# v0-cellphone.net
KiCad netlist of a schematic drawn in EAGLE
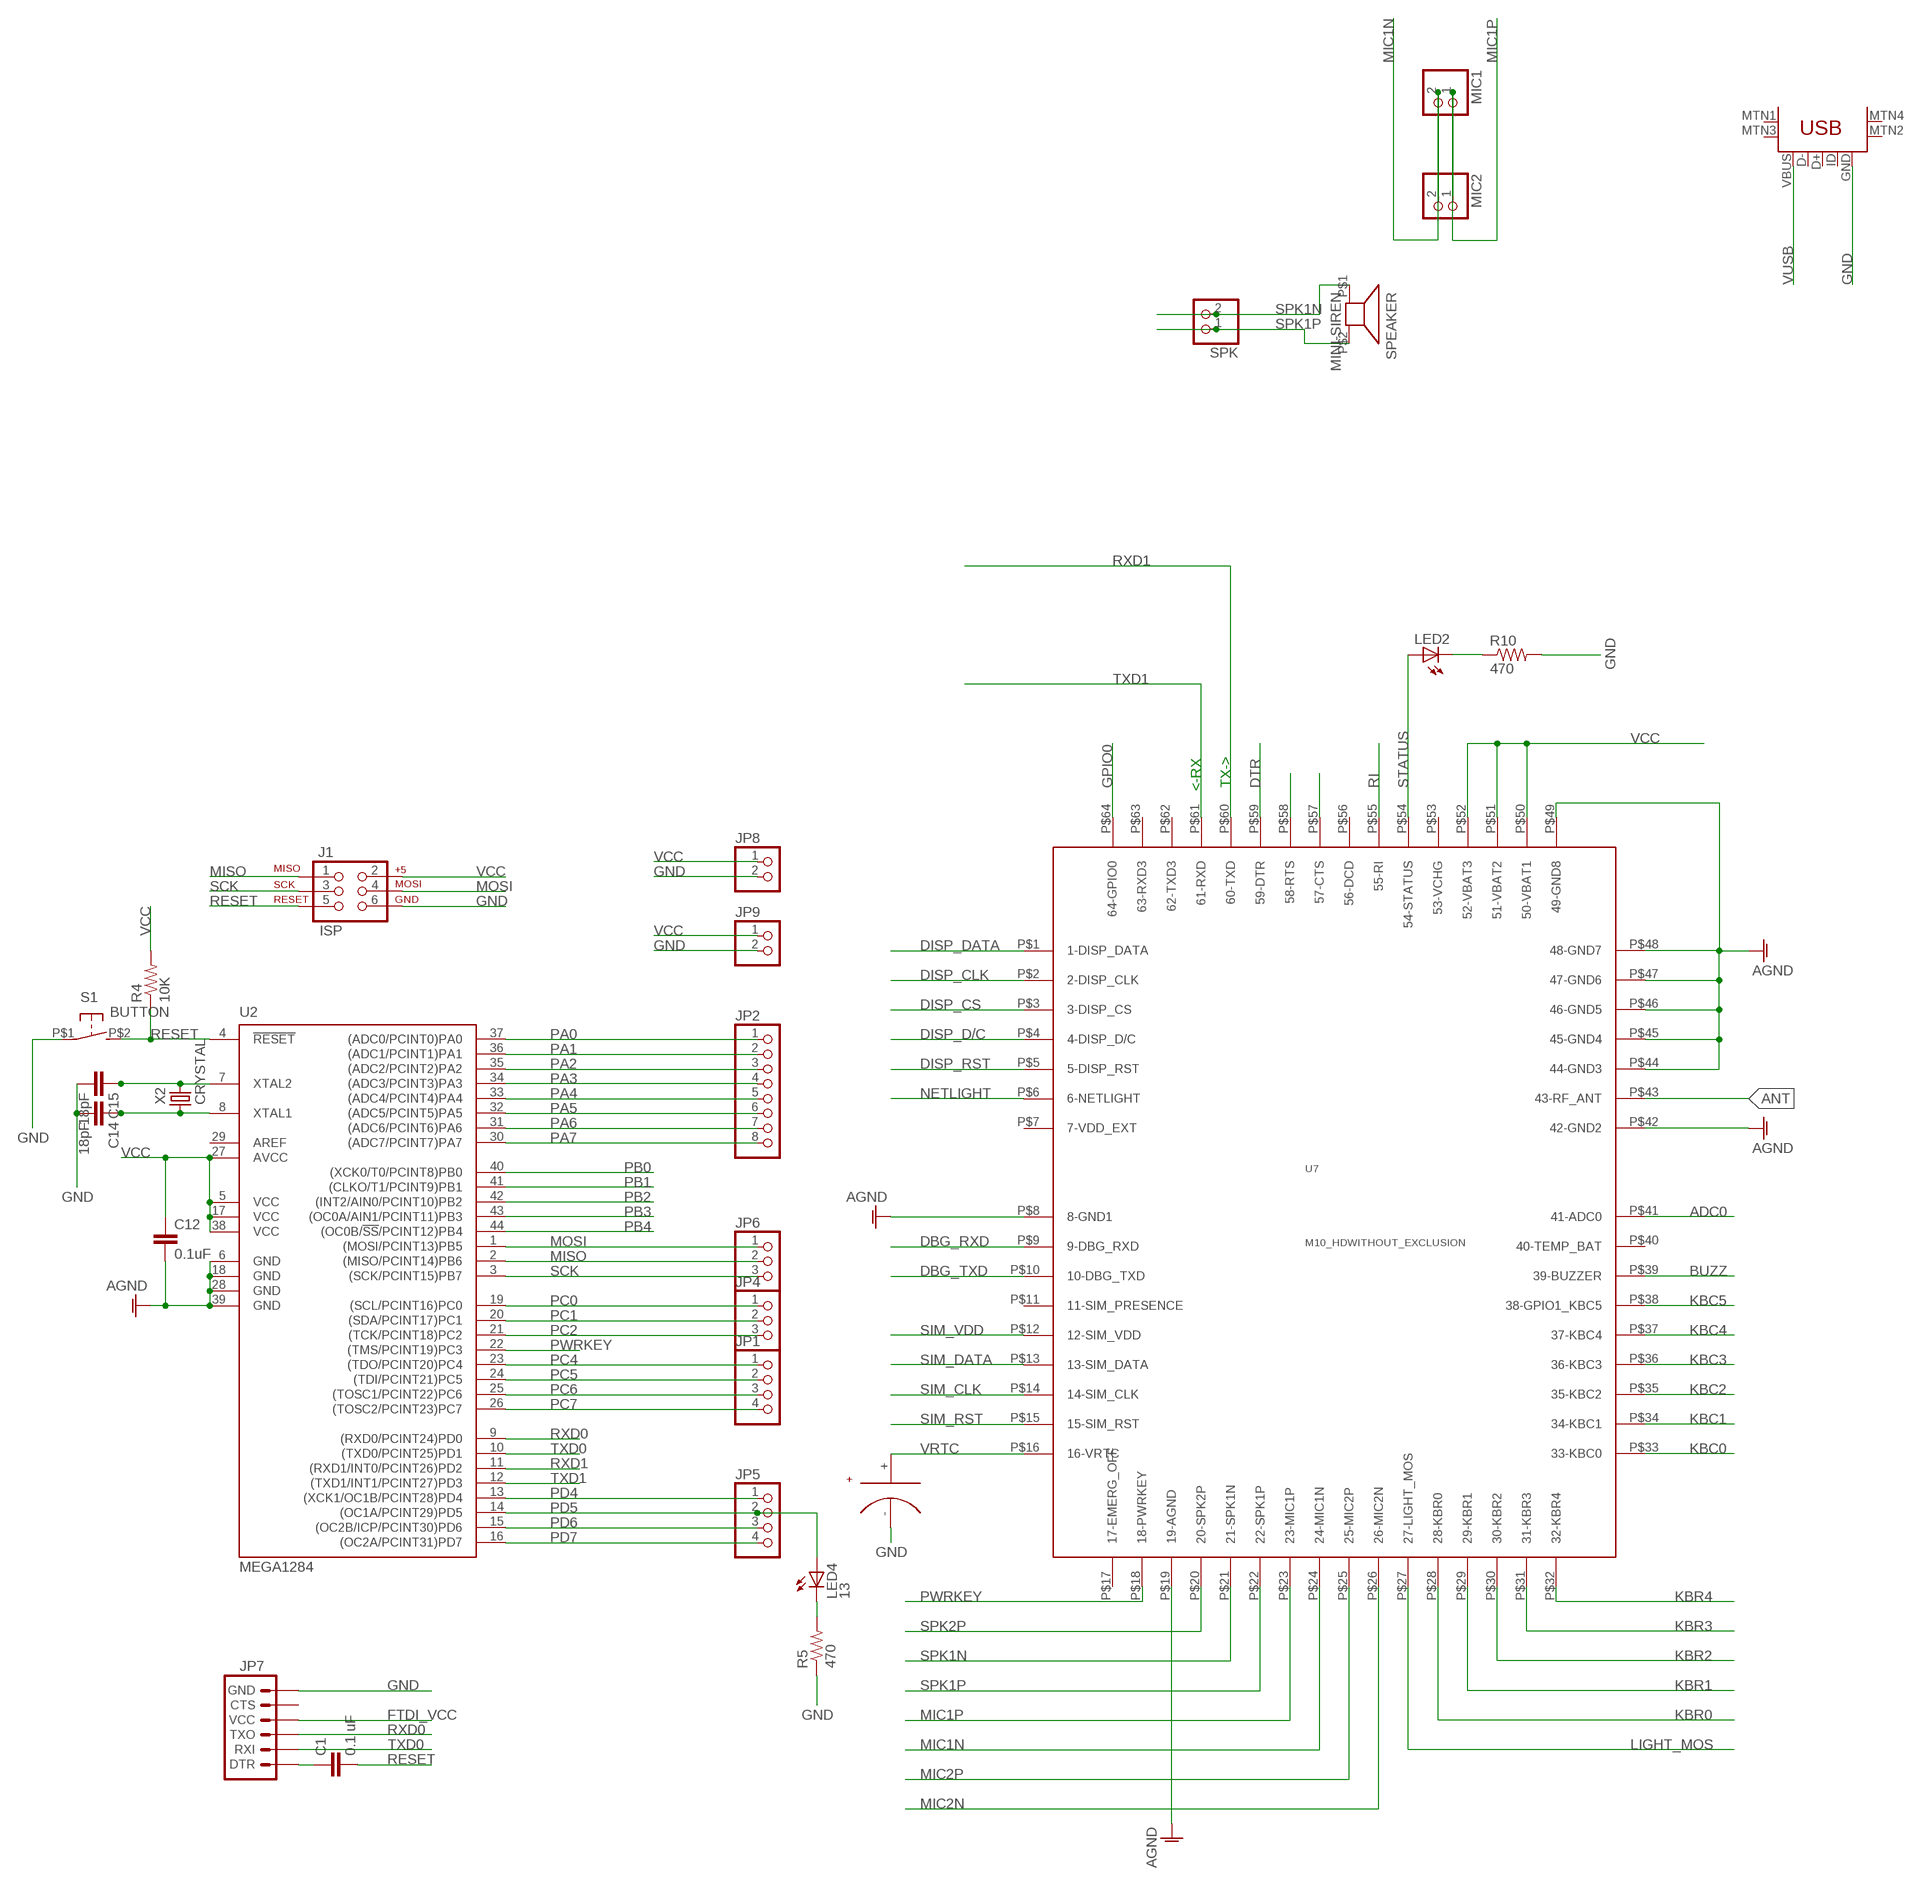
[diagram p0: schematic, sheet 1, part 1 of 2]
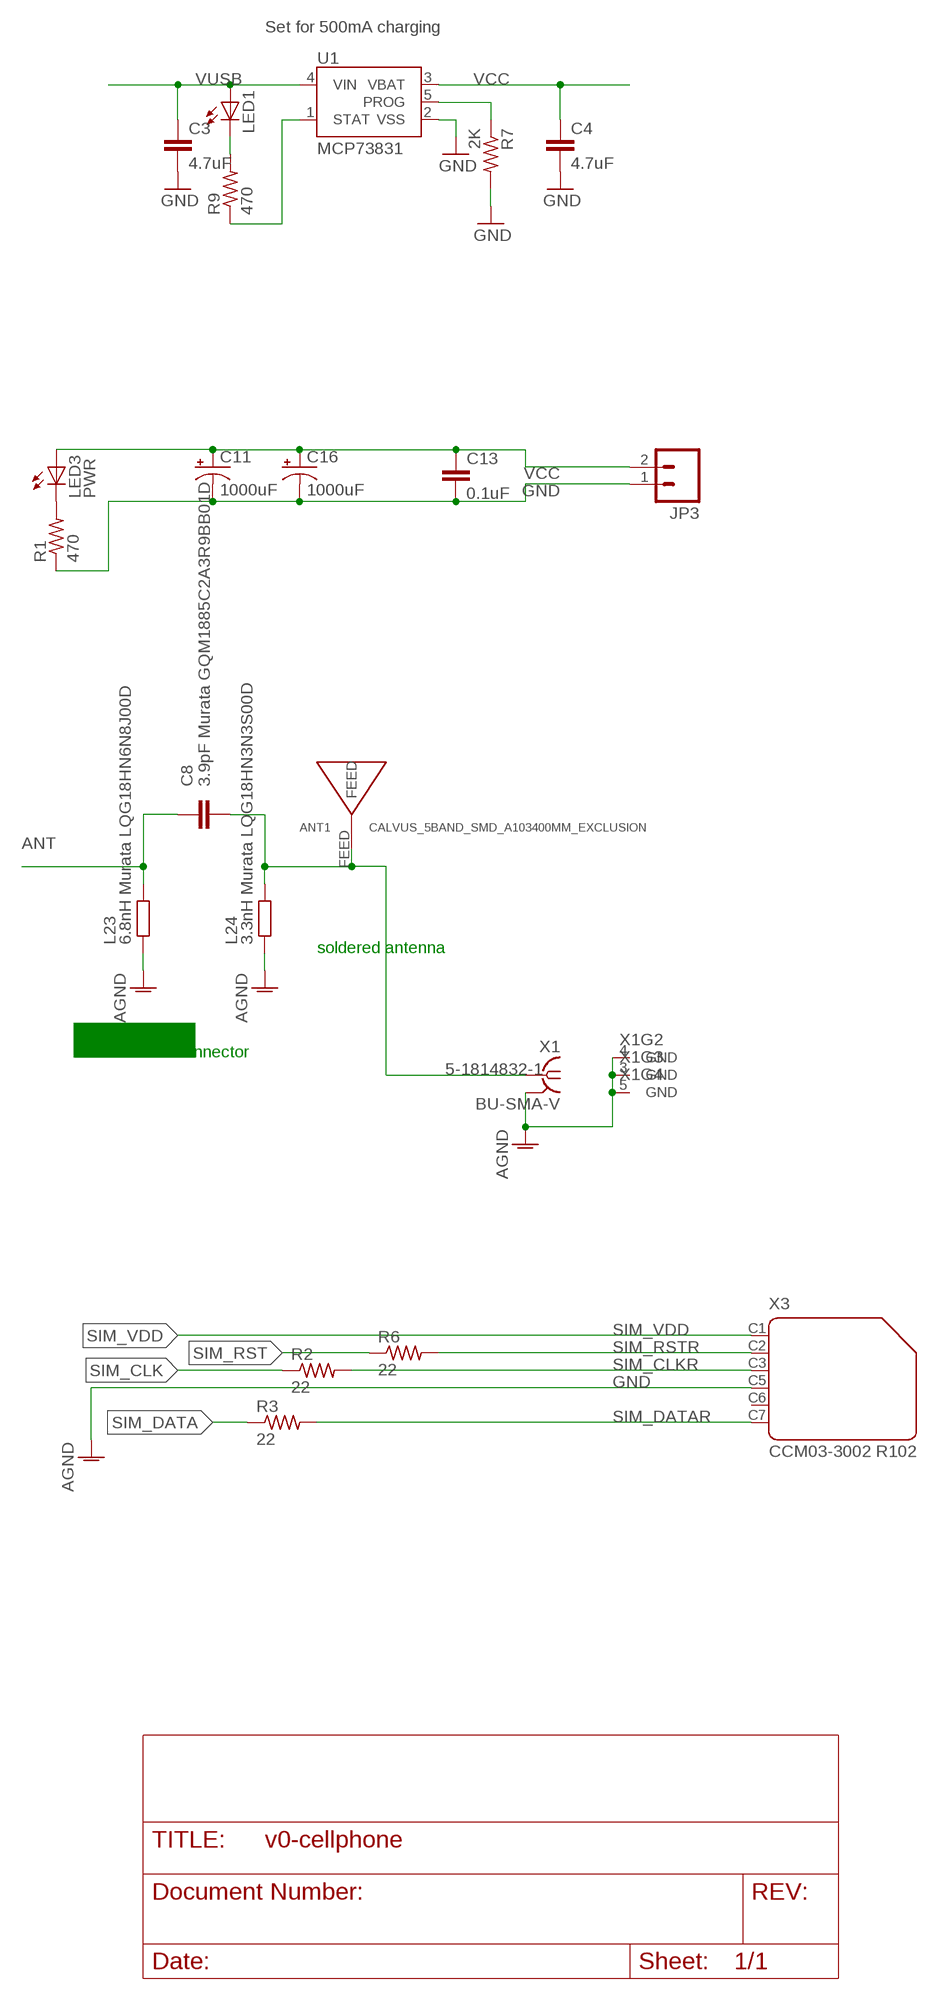
[diagram p1: schematic, sheet 1, part 2 of 2]

(export (version "E")
  (design (tool "Eeschema 10.0.6"))
  (components
    (comp (ref "ANT1")
      (value "CALVUS_5BAND_SMD_A103400MM_EXCLUSION")
      (footprint "eagle-import:CALVUS_5BAND_SMD_A10340_0MM_EXCLUSION")
      (libsource (lib "eagle-import") (part "CALVUS_5BAND_SMD_A103400MM_EXCLUSION"))
    )
    (comp (ref "C1")
      (value "0.1 uF")
      (footprint "eagle-import:C1206")
      (libsource (lib "eagle-import") (part "cellphone-rcl_C-EUC1206"))
    )
    (comp (ref "C2")
      (value "SUPERCAPPAS")
      (footprint "eagle-import:414-VA5R")
      (libsource (lib "eagle-import") (part "SUPERCAPPAS"))
    )
    (comp (ref "C3")
      (value "4.7uF")
      (footprint "eagle-import:C1206")
      (libsource (lib "eagle-import") (part "cellphone-rcl_C-EUC1206"))
    )
    (comp (ref "C4")
      (value "4.7uF")
      (footprint "eagle-import:C1206")
      (libsource (lib "eagle-import") (part "cellphone-rcl_C-EUC1206"))
    )
    (comp (ref "C8")
      (value "3.9pF Murata GQM1885C2A3R9BB01D")
      (footprint "eagle-import:C0603-ROUND")
      (libsource (lib "eagle-import") (part "C-EU0603-RND"))
    )
    (comp (ref "C11")
      (value "1000uF")
      (footprint "eagle-import:D_7343-31R")
      (libsource (lib "eagle-import") (part "CPOL-USD/7343-31R"))
    )
    (comp (ref "C12")
      (value "0.1uF")
      (footprint "eagle-import:C1206")
      (libsource (lib "eagle-import") (part "cellphone-rcl_C-EUC1206"))
    )
    (comp (ref "C13")
      (value "0.1uF")
      (footprint "eagle-import:C1206")
      (libsource (lib "eagle-import") (part "cellphone-rcl_C-EUC1206"))
    )
    (comp (ref "C14")
      (value "18pF")
      (footprint "eagle-import:C1206")
      (libsource (lib "eagle-import") (part "cellphone-rcl_C-EUC1206"))
    )
    (comp (ref "C15")
      (value "18pF")
      (footprint "eagle-import:C1206")
      (libsource (lib "eagle-import") (part "cellphone-rcl_C-EUC1206"))
    )
    (comp (ref "C16")
      (value "1000uF")
      (footprint "eagle-import:D_7343-31R")
      (libsource (lib "eagle-import") (part "CPOL-USD/7343-31R"))
    )
    (comp (ref "J1")
      (value "ISP")
      (footprint "eagle-import:2X3-NS")
      (libsource (lib "eagle-import") (part "AVR_SPI_PRG_6NS"))
    )
    (comp (ref "J2")
      (value "USB-MINIB-5PIN")
      (footprint "eagle-import:USB-MINIB")
      (libsource (lib "eagle-import") (part "USB-MINIB-5PIN"))
    )
    (comp (ref "JP1")
      (value "PINHD-1X4")
      (footprint "eagle-import:1X04")
      (libsource (lib "eagle-import") (part "PINHD-1X4"))
    )
    (comp (ref "JP2")
      (value "PINHD-1X8")
      (footprint "eagle-import:1X08")
      (libsource (lib "eagle-import") (part "PINHD-1X8"))
    )
    (comp (ref "JP3")
      (value "M02-JST-2MM-SMT")
      (footprint "eagle-import:JST-2-SMD")
      (libsource (lib "eagle-import") (part "M02-JST-2MM-SMT"))
    )
    (comp (ref "JP4")
      (value "PINHD-1X3")
      (footprint "eagle-import:1X03")
      (libsource (lib "eagle-import") (part "PINHD-1X3"))
    )
    (comp (ref "JP5")
      (value "PINHD-1X4")
      (footprint "eagle-import:1X04")
      (libsource (lib "eagle-import") (part "PINHD-1X4"))
    )
    (comp (ref "JP6")
      (value "PINHD-1X3")
      (footprint "eagle-import:1X03")
      (libsource (lib "eagle-import") (part "PINHD-1X3"))
    )
    (comp (ref "JP7")
      (value "ARDUINO_SERIAL_PROGRAMSMD-NOHOLES")
      (footprint "eagle-import:1X06-SMD-NOHOLES")
      (libsource (lib "eagle-import") (part "ARDUINO_SERIAL_PROGRAMSMD-NOHOLES"))
    )
    (comp (ref "JP8")
      (value "PINHD-1X2")
      (footprint "eagle-import:1X02")
      (libsource (lib "eagle-import") (part "PINHD-1X2"))
    )
    (comp (ref "JP9")
      (value "PINHD-1X2")
      (footprint "eagle-import:1X02")
      (libsource (lib "eagle-import") (part "PINHD-1X2"))
    )
    (comp (ref "L23")
      (value "6.8nH Murata LQG18HN6N8J00D")
      (footprint "eagle-import:R0603-ROUND")
      (libsource (lib "eagle-import") (part "R-EU_0603-RND"))
    )
    (comp (ref "L24")
      (value "3.3nH Murata LQG18HN3N3S00D")
      (footprint "eagle-import:R0603-ROUND")
      (libsource (lib "eagle-import") (part "R-EU_0603-RND"))
    )
    (comp (ref "LED1")
      (value "LEDSMT1206")
      (footprint "eagle-import:1206")
      (libsource (lib "eagle-import") (part "LEDSMT1206"))
    )
    (comp (ref "LED2")
      (value "LEDSMT1206")
      (footprint "eagle-import:1206")
      (libsource (lib "eagle-import") (part "LEDSMT1206"))
    )
    (comp (ref "LED3")
      (value "PWR")
      (footprint "eagle-import:1206")
      (libsource (lib "eagle-import") (part "LEDSMT1206"))
    )
    (comp (ref "LED4")
      (value "13")
      (footprint "eagle-import:1206")
      (libsource (lib "eagle-import") (part "LEDSMT1206"))
    )
    (comp (ref "MIC1")
      (value "PINHD-1X2")
      (footprint "eagle-import:1X02")
      (libsource (lib "eagle-import") (part "PINHD-1X2"))
    )
    (comp (ref "MIC2")
      (value "PINHD-1X2")
      (footprint "eagle-import:1X02")
      (libsource (lib "eagle-import") (part "PINHD-1X2"))
    )
    (comp (ref "R1")
      (value "470")
      (footprint "eagle-import:R1206")
      (libsource (lib "eagle-import") (part "R-US_R1206"))
    )
    (comp (ref "R2")
      (value "22")
      (footprint "eagle-import:R1206")
      (libsource (lib "eagle-import") (part "R-US_R1206"))
    )
    (comp (ref "R3")
      (value "22")
      (footprint "eagle-import:R1206")
      (libsource (lib "eagle-import") (part "R-US_R1206"))
    )
    (comp (ref "R4")
      (value "10K")
      (footprint "eagle-import:R1206")
      (libsource (lib "eagle-import") (part "R-US_R1206"))
    )
    (comp (ref "R5")
      (value "470")
      (footprint "eagle-import:R1206")
      (libsource (lib "eagle-import") (part "R-US_R1206"))
    )
    (comp (ref "R6")
      (value "22")
      (footprint "eagle-import:R1206")
      (libsource (lib "eagle-import") (part "R-US_R1206"))
    )
    (comp (ref "R7")
      (value "2K")
      (footprint "eagle-import:R1206")
      (libsource (lib "eagle-import") (part "R-US_R1206"))
    )
    (comp (ref "R9")
      (value "470")
      (footprint "eagle-import:R1206")
      (libsource (lib "eagle-import") (part "R-US_R1206"))
    )
    (comp (ref "R10")
      (value "470")
      (footprint "eagle-import:R1206")
      (libsource (lib "eagle-import") (part "R-US_R1206"))
    )
    (comp (ref "S1")
      (value "BUTTON")
      (footprint "eagle-import:B3U-1000P")
      (libsource (lib "eagle-import") (part "BUTTON-2"))
    )
    (comp (ref "SPEAKER")
      (value "MINI-SIREN")
      (footprint "eagle-import:SPEAKER-6.4MM")
      (libsource (lib "eagle-import") (part "MINI-SIREN"))
    )
    (comp (ref "SPK")
      (value "PINHD-1X2")
      (footprint "eagle-import:1X02")
      (libsource (lib "eagle-import") (part "PINHD-1X2"))
    )
    (comp (ref "U1")
      (value "MCP73831")
      (footprint "eagle-import:SOT23-5")
      (libsource (lib "eagle-import") (part "MCP73831"))
    )
    (comp (ref "U2")
      (value "MEGA1284")
      (footprint "eagle-import:TQFP44")
      (libsource (lib "eagle-import") (part "MEGA164P/324P/644P-AU"))
    )
    (comp (ref "U7")
      (value "M10_HDWITHOUT_EXCLUSION")
      (footprint "eagle-import:M10_HD_WITHOUT_EXCLUSION")
      (libsource (lib "eagle-import") (part "M10_HDWITHOUT_EXCLUSION"))
    )
    (comp (ref "X1")
      (value "BU-SMA-V")
      (footprint "eagle-import:BU-SMA-V")
      (fields (field (name "PN") "5-1814832-1"))
      (libsource (lib "eagle-import") (part "BU-SMA-V"))
    )
    (comp (ref "X2")
      (value "CRYSTAL")
      (footprint "eagle-import:2-SMD-5X3MM")
      (libsource (lib "eagle-import") (part "CRYSTAL"))
    )
    (comp (ref "X3")
      (value "CCM03-3002 R102")
      (footprint "eagle-import:CON-AMPHENOL_C707_10M006_512_2")
      (fields (field (name "OC_FARNELL") "1463072 "))
      (libsource (lib "eagle-import") (part "CON-AMPHENOL_SIMLOCK-C707_10M006_512_2"))
    )
  )
  (nets
    (net (code "1") (name "/ADC0") (class "Default")
      (node (ref "U7") (pin "P$41") (pinfunction "41-ADC0_P$41") (pintype "bidirectional"))
    )
    (net (code "2") (name "/AREF") (class "Default")
      (node (ref "U2") (pin "29") (pinfunction "AREF_29") (pintype "power_in"))
    )
    (net (code "3") (name "/BUZZ") (class "Default")
      (node (ref "U7") (pin "P$39") (pinfunction "39-BUZZER_P$39") (pintype "bidirectional"))
    )
    (net (code "4") (name "/DBG_RXD") (class "Default")
      (node (ref "U7") (pin "P$9") (pinfunction "9-DBG_RXD_P$9") (pintype "bidirectional"))
    )
    (net (code "5") (name "/DBG_TXD") (class "Default")
      (node (ref "U7") (pin "P$10") (pinfunction "10-DBG_TXD_P$10") (pintype "bidirectional"))
    )
    (net (code "6") (name "/DISP_CLK") (class "Default")
      (node (ref "U7") (pin "P$2") (pinfunction "2-DISP_CLK_P$2") (pintype "bidirectional"))
    )
    (net (code "7") (name "/DISP_CS") (class "Default")
      (node (ref "U7") (pin "P$3") (pinfunction "3-DISP_CS_P$3") (pintype "bidirectional"))
    )
    (net (code "8") (name "/DISP_DATA") (class "Default")
      (node (ref "U7") (pin "P$1") (pinfunction "1-DISP_DATA_P$1") (pintype "bidirectional"))
    )
    (net (code "9") (name "/DISP_D{slash}C") (class "Default")
      (node (ref "U7") (pin "P$4") (pinfunction "4-DISP_D/C_P$4") (pintype "bidirectional"))
    )
    (net (code "10") (name "/DISP_RST") (class "Default")
      (node (ref "U7") (pin "P$5") (pinfunction "5-DISP_RST_P$5") (pintype "bidirectional"))
    )
    (net (code "11") (name "/DTR") (class "Default")
      (node (ref "U7") (pin "P$59") (pinfunction "59-DTR_P$59") (pintype "bidirectional"))
    )
    (net (code "12") (name "/FTDI_VCC") (class "Default")
      (node (ref "JP7") (pin "4") (pinfunction "VCC_4") (pintype "passive"))
    )
    (net (code "13") (name "/GPIO0") (class "Default")
      (node (ref "U7") (pin "P$64") (pinfunction "64-GPIO0_P$64") (pintype "bidirectional"))
    )
    (net (code "14") (name "/KBC0") (class "Default")
      (node (ref "U7") (pin "P$33") (pinfunction "33-KBC0_P$33") (pintype "bidirectional"))
    )
    (net (code "15") (name "/KBC1") (class "Default")
      (node (ref "U7") (pin "P$34") (pinfunction "34-KBC1_P$34") (pintype "bidirectional"))
    )
    (net (code "16") (name "/KBC2") (class "Default")
      (node (ref "U7") (pin "P$35") (pinfunction "35-KBC2_P$35") (pintype "bidirectional"))
    )
    (net (code "17") (name "/KBC3") (class "Default")
      (node (ref "U7") (pin "P$36") (pinfunction "36-KBC3_P$36") (pintype "bidirectional"))
    )
    (net (code "18") (name "/KBC4") (class "Default")
      (node (ref "U7") (pin "P$37") (pinfunction "37-KBC4_P$37") (pintype "bidirectional"))
    )
    (net (code "19") (name "/KBC5") (class "Default")
      (node (ref "U7") (pin "P$38") (pinfunction "38-GPIO1_KBC5_P$38") (pintype "bidirectional"))
    )
    (net (code "20") (name "/KBR0") (class "Default")
      (node (ref "U7") (pin "P$28") (pinfunction "28-KBR0_P$28") (pintype "bidirectional"))
    )
    (net (code "21") (name "/KBR1") (class "Default")
      (node (ref "U7") (pin "P$29") (pinfunction "29-KBR1_P$29") (pintype "bidirectional"))
    )
    (net (code "22") (name "/KBR2") (class "Default")
      (node (ref "U7") (pin "P$30") (pinfunction "30-KBR2_P$30") (pintype "bidirectional"))
    )
    (net (code "23") (name "/KBR3") (class "Default")
      (node (ref "U7") (pin "P$31") (pinfunction "31-KBR3_P$31") (pintype "bidirectional"))
    )
    (net (code "24") (name "/KBR4") (class "Default")
      (node (ref "U7") (pin "P$32") (pinfunction "32-KBR4_P$32") (pintype "bidirectional"))
    )
    (net (code "25") (name "/LIGHT_MOS") (class "Default")
      (node (ref "U7") (pin "P$27") (pinfunction "27-LIGHT_MOS_P$27") (pintype "bidirectional"))
    )
    (net (code "26") (name "/MIC1N") (class "Default")
      (node (ref "MIC1") (pin "2") (pinfunction "2_2") (pintype "passive"))
      (node (ref "MIC2") (pin "2") (pinfunction "2_2") (pintype "passive"))
      (node (ref "U7") (pin "P$24") (pinfunction "24-MIC1N_P$24") (pintype "bidirectional"))
    )
    (net (code "27") (name "/MIC1P") (class "Default")
      (node (ref "MIC1") (pin "1") (pinfunction "1_1") (pintype "passive"))
      (node (ref "MIC2") (pin "1") (pinfunction "1_1") (pintype "passive"))
      (node (ref "U7") (pin "P$23") (pinfunction "23-MIC1P_P$23") (pintype "bidirectional"))
    )
    (net (code "28") (name "/MIC2N") (class "Default")
      (node (ref "U7") (pin "P$26") (pinfunction "26-MIC2N_P$26") (pintype "bidirectional"))
    )
    (net (code "29") (name "/MIC2P") (class "Default")
      (node (ref "U7") (pin "P$25") (pinfunction "25-MIC2P_P$25") (pintype "bidirectional"))
    )
    (net (code "30") (name "/MISO") (class "Default")
      (node (ref "J1") (pin "1") (pinfunction "1_1") (pintype "passive"))
      (node (ref "JP6") (pin "2") (pinfunction "2_2") (pintype "passive"))
      (node (ref "U2") (pin "2") (pinfunction "(MISO/PCINT14)PB6_2") (pintype "bidirectional"))
    )
    (net (code "31") (name "/MOSI") (class "Default")
      (node (ref "J1") (pin "4") (pinfunction "4_4") (pintype "passive"))
      (node (ref "JP6") (pin "1") (pinfunction "1_1") (pintype "passive"))
      (node (ref "U2") (pin "1") (pinfunction "(MOSI/PCINT13)PB5_1") (pintype "bidirectional"))
    )
    (net (code "32") (name "/NETLIGHT") (class "Default")
      (node (ref "U7") (pin "P$6") (pinfunction "6-NETLIGHT_P$6") (pintype "bidirectional"))
    )
    (net (code "33") (name "/PA0") (class "Default")
      (node (ref "JP2") (pin "1") (pinfunction "1_1") (pintype "passive"))
      (node (ref "U2") (pin "37") (pinfunction "(ADC0/PCINT0)PA0_37") (pintype "bidirectional"))
    )
    (net (code "34") (name "/PA1") (class "Default")
      (node (ref "JP2") (pin "2") (pinfunction "2_2") (pintype "passive"))
      (node (ref "U2") (pin "36") (pinfunction "(ADC1/PCINT1)PA1_36") (pintype "bidirectional"))
    )
    (net (code "35") (name "/PA2") (class "Default")
      (node (ref "JP2") (pin "3") (pinfunction "3_3") (pintype "passive"))
      (node (ref "U2") (pin "35") (pinfunction "(ADC2/PCINT2)PA2_35") (pintype "bidirectional"))
    )
    (net (code "36") (name "/PA3") (class "Default")
      (node (ref "JP2") (pin "4") (pinfunction "4_4") (pintype "passive"))
      (node (ref "U2") (pin "34") (pinfunction "(ADC3/PCINT3)PA3_34") (pintype "bidirectional"))
    )
    (net (code "37") (name "/PA4") (class "Default")
      (node (ref "JP2") (pin "5") (pinfunction "5_5") (pintype "passive"))
      (node (ref "U2") (pin "33") (pinfunction "(ADC4/PCINT4)PA4_33") (pintype "bidirectional"))
    )
    (net (code "38") (name "/PA5") (class "Default")
      (node (ref "JP2") (pin "6") (pinfunction "6_6") (pintype "passive"))
      (node (ref "U2") (pin "32") (pinfunction "(ADC5/PCINT5)PA5_32") (pintype "bidirectional"))
    )
    (net (code "39") (name "/PA6") (class "Default")
      (node (ref "JP2") (pin "7") (pinfunction "7_7") (pintype "passive"))
      (node (ref "U2") (pin "31") (pinfunction "(ADC6/PCINT6)PA6_31") (pintype "bidirectional"))
    )
    (net (code "40") (name "/PA7") (class "Default")
      (node (ref "JP2") (pin "8") (pinfunction "8_8") (pintype "passive"))
      (node (ref "U2") (pin "30") (pinfunction "(ADC7/PCINT7)PA7_30") (pintype "bidirectional"))
    )
    (net (code "41") (name "/PB0") (class "Default")
      (node (ref "U2") (pin "40") (pinfunction "(XCK0/T0/PCINT8)PB0_40") (pintype "bidirectional"))
    )
    (net (code "42") (name "/PB1") (class "Default")
      (node (ref "U2") (pin "41") (pinfunction "(CLKO/T1/PCINT9)PB1_41") (pintype "bidirectional"))
    )
    (net (code "43") (name "/PB2") (class "Default")
      (node (ref "U2") (pin "42") (pinfunction "(INT2/AIN0/PCINT10)PB2_42") (pintype "bidirectional"))
    )
    (net (code "44") (name "/PB3") (class "Default")
      (node (ref "U2") (pin "43") (pinfunction "(OC0A/AIN1/PCINT11)PB3_43") (pintype "bidirectional"))
    )
    (net (code "45") (name "/PB4") (class "Default")
      (node (ref "U2") (pin "44") (pinfunction "(OC0B/~{SS}/PCINT12)PB4_44") (pintype "bidirectional"))
    )
    (net (code "46") (name "/PC0") (class "Default")
      (node (ref "JP4") (pin "1") (pinfunction "1_1") (pintype "passive"))
      (node (ref "U2") (pin "19") (pinfunction "(SCL/PCINT16)PC0_19") (pintype "bidirectional"))
    )
    (net (code "47") (name "/PC1") (class "Default")
      (node (ref "JP4") (pin "2") (pinfunction "2_2") (pintype "passive"))
      (node (ref "U2") (pin "20") (pinfunction "(SDA/PCINT17)PC1_20") (pintype "bidirectional"))
    )
    (net (code "48") (name "/PC2") (class "Default")
      (node (ref "JP4") (pin "3") (pinfunction "3_3") (pintype "passive"))
      (node (ref "U2") (pin "21") (pinfunction "(TCK/PCINT18)PC2_21") (pintype "bidirectional"))
    )
    (net (code "49") (name "/PC4") (class "Default")
      (node (ref "JP1") (pin "1") (pinfunction "1_1") (pintype "passive"))
      (node (ref "U2") (pin "23") (pinfunction "(TDO/PCINT20)PC4_23") (pintype "bidirectional"))
    )
    (net (code "50") (name "/PC5") (class "Default")
      (node (ref "JP1") (pin "2") (pinfunction "2_2") (pintype "passive"))
      (node (ref "U2") (pin "24") (pinfunction "(TDI/PCINT21)PC5_24") (pintype "bidirectional"))
    )
    (net (code "51") (name "/PC6") (class "Default")
      (node (ref "JP1") (pin "3") (pinfunction "3_3") (pintype "passive"))
      (node (ref "U2") (pin "25") (pinfunction "(TOSC1/PCINT22)PC6_25") (pintype "bidirectional"))
    )
    (net (code "52") (name "/PC7") (class "Default")
      (node (ref "JP1") (pin "4") (pinfunction "4_4") (pintype "passive"))
      (node (ref "U2") (pin "26") (pinfunction "(TOSC2/PCINT23)PC7_26") (pintype "bidirectional"))
    )
    (net (code "53") (name "/PD4") (class "Default")
      (node (ref "JP5") (pin "1") (pinfunction "1_1") (pintype "passive"))
      (node (ref "U2") (pin "13") (pinfunction "(XCK1/OC1B/PCINT28)PD4_13") (pintype "bidirectional"))
    )
    (net (code "54") (name "/PD5") (class "Default")
      (node (ref "JP5") (pin "2") (pinfunction "2_2") (pintype "passive"))
      (node (ref "LED4") (pin "A") (pinfunction "A_A") (pintype "passive"))
      (node (ref "U2") (pin "14") (pinfunction "(OC1A/PCINT29)PD5_14") (pintype "bidirectional"))
    )
    (net (code "55") (name "/PD6") (class "Default")
      (node (ref "JP5") (pin "3") (pinfunction "3_3") (pintype "passive"))
      (node (ref "U2") (pin "15") (pinfunction "(OC2B/ICP/PCINT30)PD6_15") (pintype "bidirectional"))
    )
    (net (code "56") (name "/PD7") (class "Default")
      (node (ref "JP5") (pin "4") (pinfunction "4_4") (pintype "passive"))
      (node (ref "U2") (pin "16") (pinfunction "(OC2A/PCINT31)PD7_16") (pintype "bidirectional"))
    )
    (net (code "57") (name "/PWRKEY") (class "Default")
      (node (ref "U2") (pin "22") (pinfunction "(TMS/PCINT19)PC3_22") (pintype "bidirectional"))
      (node (ref "U7") (pin "P$18") (pinfunction "18-PWRKEY_P$18") (pintype "bidirectional"))
    )
    (net (code "58") (name "/RESET") (class "Default")
      (node (ref "C1") (pin "2") (pinfunction "2_2") (pintype "passive"))
      (node (ref "J1") (pin "5") (pinfunction "5_5") (pintype "passive"))
      (node (ref "R4") (pin "1") (pinfunction "1_1") (pintype "passive"))
      (node (ref "S1") (pin "P$2") (pinfunction "S_P$2") (pintype "passive"))
      (node (ref "U2") (pin "4") (pinfunction "~{RESET}_4") (pintype "input"))
    )
    (net (code "59") (name "/RI") (class "Default")
      (node (ref "U7") (pin "P$55") (pinfunction "55-RI_P$55") (pintype "bidirectional"))
    )
    (net (code "60") (name "/RXD0") (class "Default")
      (node (ref "JP7") (pin "3") (pinfunction "TXO_3") (pintype "passive"))
      (node (ref "U2") (pin "9") (pinfunction "(RXD0/PCINT24)PD0_9") (pintype "bidirectional"))
    )
    (net (code "61") (name "/RXD1") (class "Default")
      (node (ref "U2") (pin "11") (pinfunction "(RXD1/INT0/PCINT26)PD2_11") (pintype "bidirectional"))
      (node (ref "U7") (pin "P$60") (pinfunction "60-TXD_P$60") (pintype "bidirectional"))
    )
    (net (code "62") (name "/SCK") (class "Default")
      (node (ref "J1") (pin "3") (pinfunction "3_3") (pintype "passive"))
      (node (ref "JP6") (pin "3") (pinfunction "3_3") (pintype "passive"))
      (node (ref "U2") (pin "3") (pinfunction "(SCK/PCINT15)PB7_3") (pintype "bidirectional"))
    )
    (net (code "63") (name "/SIM_CLKR") (class "Default")
      (node (ref "R2") (pin "2") (pinfunction "2_2") (pintype "passive"))
      (node (ref "X3") (pin "C3") (pinfunction "3_C3") (pintype "passive"))
    )
    (net (code "64") (name "/SIM_DATAR") (class "Default")
      (node (ref "R3") (pin "2") (pinfunction "2_2") (pintype "passive"))
      (node (ref "X3") (pin "C7") (pinfunction "6_C7") (pintype "passive"))
    )
    (net (code "65") (name "/SIM_RSTR") (class "Default")
      (node (ref "R6") (pin "2") (pinfunction "2_2") (pintype "passive"))
      (node (ref "X3") (pin "C2") (pinfunction "2_C2") (pintype "passive"))
    )
    (net (code "66") (name "/SPK1N") (class "Default")
      (node (ref "SPEAKER") (pin "P$1") (pinfunction "1_P$1") (pintype "passive"))
      (node (ref "SPK") (pin "2") (pinfunction "2_2") (pintype "passive"))
      (node (ref "U7") (pin "P$21") (pinfunction "21-SPK1N_P$21") (pintype "bidirectional"))
    )
    (net (code "67") (name "/SPK1P") (class "Default")
      (node (ref "SPEAKER") (pin "P$2") (pinfunction "2_P$2") (pintype "passive"))
      (node (ref "SPK") (pin "1") (pinfunction "1_1") (pintype "passive"))
      (node (ref "U7") (pin "P$22") (pinfunction "22-SPK1P_P$22") (pintype "bidirectional"))
    )
    (net (code "68") (name "/SPK2P") (class "Default")
      (node (ref "U7") (pin "P$20") (pinfunction "20-SPK2P_P$20") (pintype "bidirectional"))
    )
    (net (code "69") (name "/STATUS") (class "Default")
      (node (ref "LED2") (pin "A") (pinfunction "A_A") (pintype "passive"))
      (node (ref "U7") (pin "P$54") (pinfunction "54-STATUS_P$54") (pintype "bidirectional"))
    )
    (net (code "70") (name "/TXD0") (class "Default")
      (node (ref "JP7") (pin "2") (pinfunction "RXI_2") (pintype "passive"))
      (node (ref "U2") (pin "10") (pinfunction "(TXD0/PCINT25)PD1_10") (pintype "bidirectional"))
    )
    (net (code "71") (name "/TXD1") (class "Default")
      (node (ref "U2") (pin "12") (pinfunction "(TXD1/INT1/PCINT27)PD3_12") (pintype "bidirectional"))
      (node (ref "U7") (pin "P$61") (pinfunction "61-RXD_P$61") (pintype "bidirectional"))
    )
    (net (code "72") (name "/VCC") (class "Default")
      (node (ref "C11") (pin "+") (pinfunction "+_+") (pintype "passive"))
      (node (ref "C12") (pin "1") (pinfunction "1_1") (pintype "passive"))
      (node (ref "C13") (pin "1") (pinfunction "1_1") (pintype "passive"))
      (node (ref "C16") (pin "+") (pinfunction "+_+") (pintype "passive"))
      (node (ref "C4") (pin "1") (pinfunction "1_1") (pintype "passive"))
      (node (ref "J1") (pin "2") (pinfunction "2_2") (pintype "passive"))
      (node (ref "JP3") (pin "2") (pinfunction "1_2") (pintype "passive"))
      (node (ref "JP8") (pin "1") (pinfunction "1_1") (pintype "passive"))
      (node (ref "JP9") (pin "1") (pinfunction "1_1") (pintype "passive"))
      (node (ref "LED3") (pin "A") (pinfunction "A_A") (pintype "passive"))
      (node (ref "R4") (pin "2") (pinfunction "2_2") (pintype "passive"))
      (node (ref "U1") (pin "3") (pinfunction "VBAT_3") (pintype "power_in"))
      (node (ref "U2") (pin "17") (pinfunction "VCC_17") (pintype "power_in"))
      (node (ref "U2") (pin "27") (pinfunction "AVCC_27") (pintype "power_in"))
      (node (ref "U2") (pin "38") (pinfunction "VCC_38") (pintype "power_in"))
      (node (ref "U2") (pin "5") (pinfunction "VCC_5") (pintype "power_in"))
      (node (ref "U7") (pin "P$50") (pinfunction "50-VBAT1_P$50") (pintype "bidirectional"))
      (node (ref "U7") (pin "P$51") (pinfunction "51-VBAT2_P$51") (pintype "bidirectional"))
      (node (ref "U7") (pin "P$52") (pinfunction "52-VBAT3_P$52") (pintype "bidirectional"))
    )
    (net (code "73") (name "/VRTC") (class "Default")
      (node (ref "C2") (pin "+") (pinfunction "+_+") (pintype "bidirectional"))
      (node (ref "U7") (pin "P$16") (pinfunction "16-VRTC_P$16") (pintype "bidirectional"))
    )
    (net (code "74") (name "/VUSB") (class "Default")
      (node (ref "C3") (pin "1") (pinfunction "1_1") (pintype "passive"))
      (node (ref "J2") (pin "VBUS") (pinfunction "VBUS_VBUS") (pintype "bidirectional"))
      (node (ref "LED1") (pin "A") (pinfunction "A_A") (pintype "passive"))
      (node (ref "U1") (pin "4") (pinfunction "VIN_4") (pintype "power_in"))
    )
    (net (code "75") (name "AGND") (class "Default")
      (node (ref "C11") (pin "-") (pinfunction "-_-") (pintype "passive"))
      (node (ref "C12") (pin "2") (pinfunction "2_2") (pintype "passive"))
      (node (ref "C13") (pin "2") (pinfunction "2_2") (pintype "passive"))
      (node (ref "C14") (pin "2") (pinfunction "2_2") (pintype "passive"))
      (node (ref "C15") (pin "2") (pinfunction "2_2") (pintype "passive"))
      (node (ref "C16") (pin "-") (pinfunction "-_-") (pintype "passive"))
      (node (ref "C2") (pin "-") (pinfunction "-_-") (pintype "bidirectional"))
      (node (ref "C3") (pin "2") (pinfunction "2_2") (pintype "passive"))
      (node (ref "C4") (pin "2") (pinfunction "2_2") (pintype "passive"))
      (node (ref "J1") (pin "6") (pinfunction "6_6") (pintype "passive"))
      (node (ref "J2") (pin "GND") (pinfunction "GND_GND") (pintype "bidirectional"))
      (node (ref "JP3") (pin "1") (pinfunction "2_1") (pintype "passive"))
      (node (ref "JP7") (pin "6") (pinfunction "GND_6") (pintype "passive"))
      (node (ref "JP8") (pin "2") (pinfunction "2_2") (pintype "passive"))
      (node (ref "JP9") (pin "2") (pinfunction "2_2") (pintype "passive"))
      (node (ref "L23") (pin "1") (pinfunction "1_1") (pintype "passive"))
      (node (ref "L24") (pin "1") (pinfunction "1_1") (pintype "passive"))
      (node (ref "R1") (pin "1") (pinfunction "1_1") (pintype "passive"))
      (node (ref "R10") (pin "2") (pinfunction "2_2") (pintype "passive"))
      (node (ref "R5") (pin "1") (pinfunction "1_1") (pintype "passive"))
      (node (ref "R7") (pin "2") (pinfunction "2_2") (pintype "passive"))
      (node (ref "S1") (pin "P$1") (pinfunction "P_P$1") (pintype "passive"))
      (node (ref "U1") (pin "2") (pinfunction "VSS_2") (pintype "power_in"))
      (node (ref "U2") (pin "18") (pinfunction "GND_18") (pintype "power_in"))
      (node (ref "U2") (pin "28") (pinfunction "GND_28") (pintype "power_in"))
      (node (ref "U2") (pin "39") (pinfunction "GND_39") (pintype "power_in"))
      (node (ref "U2") (pin "6") (pinfunction "GND_6") (pintype "power_in"))
      (node (ref "U7") (pin "P$19") (pinfunction "19-AGND_P$19") (pintype "bidirectional"))
      (node (ref "U7") (pin "P$42") (pinfunction "42-GND2_P$42") (pintype "bidirectional"))
      (node (ref "U7") (pin "P$44") (pinfunction "44-GND3_P$44") (pintype "bidirectional"))
      (node (ref "U7") (pin "P$45") (pinfunction "45-GND4_P$45") (pintype "bidirectional"))
      (node (ref "U7") (pin "P$46") (pinfunction "46-GND5_P$46") (pintype "bidirectional"))
      (node (ref "U7") (pin "P$47") (pinfunction "47-GND6_P$47") (pintype "bidirectional"))
      (node (ref "U7") (pin "P$48") (pinfunction "48-GND7_P$48") (pintype "bidirectional"))
      (node (ref "U7") (pin "P$49") (pinfunction "49-GND8_P$49") (pintype "bidirectional"))
      (node (ref "U7") (pin "P$8") (pinfunction "8-GND1_P$8") (pintype "bidirectional"))
      (node (ref "X1") (pin "2") (pinfunction "GND_2") (pintype "power_in"))
      (node (ref "X1") (pin "3") (pinfunction "GND_3") (pintype "power_in"))
      (node (ref "X1") (pin "4") (pinfunction "GND_4") (pintype "power_in"))
      (node (ref "X1") (pin "5") (pinfunction "GND_5") (pintype "power_in"))
      (node (ref "X3") (pin "C5") (pinfunction "4_C5") (pintype "passive"))
    )
    (net (code "76") (name "ANT") (class "Default")
      (node (ref "C8") (pin "1") (pinfunction "1_1") (pintype "passive"))
      (node (ref "L23") (pin "2") (pinfunction "2_2") (pintype "passive"))
      (node (ref "U7") (pin "P$43") (pinfunction "43-RF_ANT_P$43") (pintype "bidirectional"))
    )
    (net (code "77") (name "Net-(ANT1-PadFEED)") (class "Default")
      (node (ref "ANT1") (pin "FEED") (pinfunction "FEED_FEED") (pintype "bidirectional"))
      (node (ref "C8") (pin "2") (pinfunction "2_2") (pintype "passive"))
      (node (ref "L24") (pin "2") (pinfunction "2_2") (pintype "passive"))
      (node (ref "X1") (pin "1") (pinfunction "1_1") (pintype "passive"))
    )
    (net (code "78") (name "Net-(JP7-DTR)") (class "Default")
      (node (ref "C1") (pin "1") (pinfunction "1_1") (pintype "passive"))
      (node (ref "JP7") (pin "1") (pinfunction "DTR_1") (pintype "passive"))
    )
    (net (code "79") (name "Net-(LED1-PadC)") (class "Default")
      (node (ref "LED1") (pin "C") (pinfunction "C_C") (pintype "passive"))
      (node (ref "R9") (pin "2") (pinfunction "2_2") (pintype "passive"))
    )
    (net (code "80") (name "Net-(LED2-PadC)") (class "Default")
      (node (ref "LED2") (pin "C") (pinfunction "C_C") (pintype "passive"))
      (node (ref "R10") (pin "1") (pinfunction "1_1") (pintype "passive"))
    )
    (net (code "81") (name "Net-(LED3-PadC)") (class "Default")
      (node (ref "LED3") (pin "C") (pinfunction "C_C") (pintype "passive"))
      (node (ref "R1") (pin "2") (pinfunction "2_2") (pintype "passive"))
    )
    (net (code "82") (name "Net-(LED4-PadC)") (class "Default")
      (node (ref "LED4") (pin "C") (pinfunction "C_C") (pintype "passive"))
      (node (ref "R5") (pin "2") (pinfunction "2_2") (pintype "passive"))
    )
    (net (code "83") (name "Net-(U1-PROG)") (class "Default")
      (node (ref "R7") (pin "1") (pinfunction "1_1") (pintype "passive"))
      (node (ref "U1") (pin "5") (pinfunction "PROG_5") (pintype "input"))
    )
    (net (code "84") (name "Net-(U1-STAT)") (class "Default")
      (node (ref "R9") (pin "1") (pinfunction "1_1") (pintype "passive"))
      (node (ref "U1") (pin "1") (pinfunction "STAT_1") (pintype "output"))
    )
    (net (code "85") (name "Net-(U2-XTAL1)") (class "Default")
      (node (ref "C14") (pin "1") (pinfunction "1_1") (pintype "passive"))
      (node (ref "U2") (pin "8") (pinfunction "XTAL1_8") (pintype "input"))
      (node (ref "X2") (pin "P$1") (pinfunction "1_P$1") (pintype "passive"))
    )
    (net (code "86") (name "Net-(U2-XTAL2)") (class "Default")
      (node (ref "C15") (pin "1") (pinfunction "1_1") (pintype "passive"))
      (node (ref "U2") (pin "7") (pinfunction "XTAL2_7") (pintype "output"))
      (node (ref "X2") (pin "P$2") (pinfunction "2_P$2") (pintype "passive"))
    )
    (net (code "87") (name "SIM_CLK") (class "Default")
      (node (ref "R2") (pin "1") (pinfunction "1_1") (pintype "passive"))
      (node (ref "U7") (pin "P$14") (pinfunction "14-SIM_CLK_P$14") (pintype "bidirectional"))
    )
    (net (code "88") (name "SIM_DATA") (class "Default")
      (node (ref "R3") (pin "1") (pinfunction "1_1") (pintype "passive"))
      (node (ref "U7") (pin "P$13") (pinfunction "13-SIM_DATA_P$13") (pintype "bidirectional"))
    )
    (net (code "89") (name "SIM_RST") (class "Default")
      (node (ref "R6") (pin "1") (pinfunction "1_1") (pintype "passive"))
      (node (ref "U7") (pin "P$15") (pinfunction "15-SIM_RST_P$15") (pintype "bidirectional"))
    )
    (net (code "90") (name "SIM_VDD") (class "Default")
      (node (ref "U7") (pin "P$12") (pinfunction "12-SIM_VDD_P$12") (pintype "bidirectional"))
      (node (ref "X3") (pin "C1") (pinfunction "1_C1") (pintype "passive"))
    )
    (net (code "91") (name "unconnected-(J2-MTN1-PadMTN3)") (class "Default")
      (node (ref "J2") (pin "MTN3") (pinfunction "MTN1_MTN3") (pintype "bidirectional"))
    )
    (net (code "92") (name "unconnected-(J2-MTN2-PadMTN1)") (class "Default")
      (node (ref "J2") (pin "MTN1") (pinfunction "MTN2_MTN1") (pintype "bidirectional"))
    )
    (net (code "93") (name "unconnected-(J2-MTN3-PadMTN2)") (class "Default")
      (node (ref "J2") (pin "MTN2") (pinfunction "MTN3_MTN2") (pintype "bidirectional"))
    )
    (net (code "94") (name "unconnected-(J2-PadD+)") (class "Default")
      (node (ref "J2") (pin "D+") (pinfunction "D+_D+") (pintype "bidirectional"))
    )
    (net (code "95") (name "unconnected-(J2-PadD-)") (class "Default")
      (node (ref "J2") (pin "D-") (pinfunction "D-_D-") (pintype "bidirectional"))
    )
    (net (code "96") (name "unconnected-(J2-PadID)") (class "Default")
      (node (ref "J2") (pin "ID") (pinfunction "ID_ID") (pintype "bidirectional"))
    )
    (net (code "97") (name "unconnected-(J2-PadMTN4)") (class "Default")
      (node (ref "J2") (pin "MTN4") (pinfunction "MTN4_MTN4") (pintype "bidirectional"))
    )
    (net (code "98") (name "unconnected-(JP7-CTS-Pad5)") (class "Default")
      (node (ref "JP7") (pin "5") (pinfunction "CTS_5") (pintype "passive"))
    )
    (net (code "99") (name "unconnected-(U7-7-VDD_EXT-PadP$7)") (class "Default")
      (node (ref "U7") (pin "P$7") (pinfunction "7-VDD_EXT_P$7") (pintype "bidirectional"))
    )
    (net (code "100") (name "unconnected-(U7-11-SIM_PRESENCE-PadP$11)") (class "Default")
      (node (ref "U7") (pin "P$11") (pinfunction "11-SIM_PRESENCE_P$11") (pintype "bidirectional"))
    )
    (net (code "101") (name "unconnected-(U7-17-EMERG_OFF-PadP$17)") (class "Default")
      (node (ref "U7") (pin "P$17") (pinfunction "17-EMERG_OFF_P$17") (pintype "bidirectional"))
    )
    (net (code "102") (name "unconnected-(U7-40-TEMP_BAT-PadP$40)") (class "Default")
      (node (ref "U7") (pin "P$40") (pinfunction "40-TEMP_BAT_P$40") (pintype "bidirectional"))
    )
    (net (code "103") (name "unconnected-(U7-53-VCHG-PadP$53)") (class "Default")
      (node (ref "U7") (pin "P$53") (pinfunction "53-VCHG_P$53") (pintype "bidirectional"))
    )
    (net (code "104") (name "unconnected-(U7-56-DCD-PadP$56)") (class "Default")
      (node (ref "U7") (pin "P$56") (pinfunction "56-DCD_P$56") (pintype "bidirectional"))
    )
    (net (code "105") (name "unconnected-(U7-57-CTS-PadP$57)") (class "Default")
      (node (ref "U7") (pin "P$57") (pinfunction "57-CTS_P$57") (pintype "bidirectional"))
    )
    (net (code "106") (name "unconnected-(U7-58-RTS-PadP$58)") (class "Default")
      (node (ref "U7") (pin "P$58") (pinfunction "58-RTS_P$58") (pintype "bidirectional"))
    )
    (net (code "107") (name "unconnected-(U7-62-TXD3-PadP$62)") (class "Default")
      (node (ref "U7") (pin "P$62") (pinfunction "62-TXD3_P$62") (pintype "bidirectional"))
    )
    (net (code "108") (name "unconnected-(U7-63-RXD3-PadP$63)") (class "Default")
      (node (ref "U7") (pin "P$63") (pinfunction "63-RXD3_P$63") (pintype "bidirectional"))
    )
    (net (code "109") (name "unconnected-(X3-5-PadC6)") (class "Default")
      (node (ref "X3") (pin "C6") (pinfunction "5_C6") (pintype "passive"))
    )
  )
)
